# B-CAN-giraffe_v1.net
KiCad netlist of a schematic drawn in EAGLE
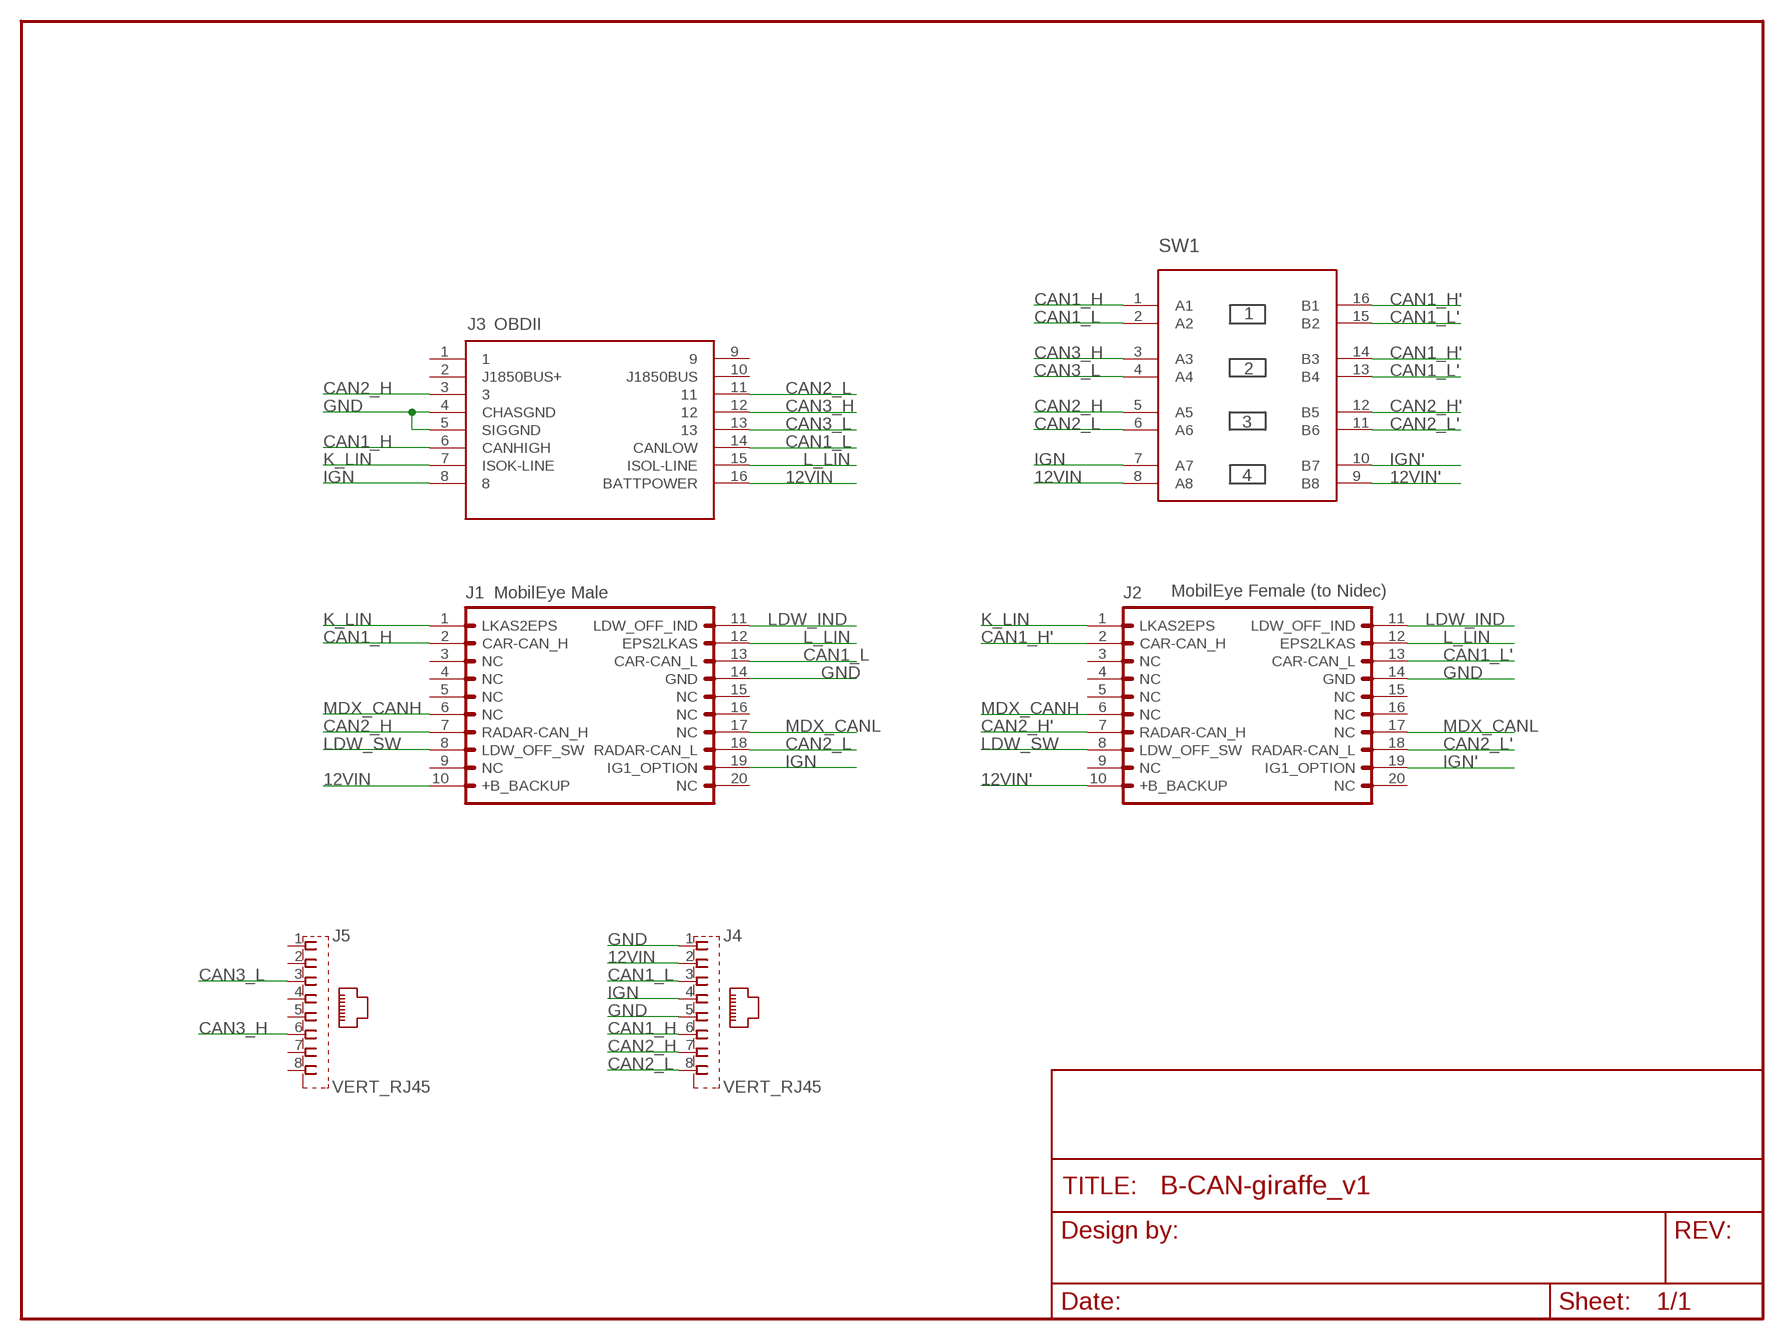
[diagram p0: schematic, sheet 1]

(export (version "E")
  (design (tool "Eeschema 10.0.6"))
  (components
    (comp (ref "FRAME1")
      (value "FRAME-LETTERNO_PACKAGE")
      (footprint "eagle-import:DUMMY")
      (fields (field (name "DESIGNER") "Nobody"))
      (libsource (lib "eagle-import") (part "FRAME-LETTERNO_PACKAGE"))
    )
    (comp (ref "J1")
      (value "MOBILEYERAMALE")
      (footprint "eagle-import:2X10(RA)")
      (libsource (lib "eagle-import") (part "MOBILEYERAMALE"))
    )
    (comp (ref "J2")
      (value "MOBILEYEFEMALE")
      (footprint "eagle-import:2X10(JAE_FEMALE)")
      (libsource (lib "eagle-import") (part "MOBILEYEFEMALE"))
    )
    (comp (ref "J3")
      (value "OBDII-FEMALE-CUT")
      (footprint "eagle-import:OBDII-FEMALE-MIDCUT")
      (libsource (lib "eagle-import") (part "OBDII-FEMALE-CUT"))
    )
    (comp (ref "J4")
      (value "VERT_RJ45")
      (footprint "eagle-import:GLX-S-88M")
      (libsource (lib "eagle-import") (part "VERT_RJ45"))
    )
    (comp (ref "J5")
      (value "VERT_RJ45")
      (footprint "eagle-import:GLX-S-88M")
      (libsource (lib "eagle-import") (part "comma.ai_2652900_VERT_RJ45"))
    )
    (comp (ref "SW1")
      (value "4XDPSTSMT")
      (footprint "eagle-import:4-DPST")
      (libsource (lib "eagle-import") (part "4XDPSTSMT"))
    )
  )
  (nets
    (net (code "1") (name "/12VIN") (class "Default")
      (node (ref "J1") (pin "10") (pinfunction "+B_BACKUP_10") (pintype "bidirectional"))
      (node (ref "J3") (pin "16") (pinfunction "BATTPOWER_16") (pintype "bidirectional"))
      (node (ref "J4") (pin "2") (pinfunction "2_2") (pintype "passive"))
      (node (ref "SW1") (pin "8") (pinfunction "A8_8") (pintype "bidirectional"))
    )
    (net (code "2") (name "/12VIN'") (class "Default")
      (node (ref "J2") (pin "10") (pinfunction "+B_BACKUP_10") (pintype "bidirectional"))
      (node (ref "SW1") (pin "9") (pinfunction "B8_9") (pintype "bidirectional"))
    )
    (net (code "3") (name "/CAN1_H") (class "Default")
      (node (ref "J1") (pin "2") (pinfunction "CAR-CAN_H_2") (pintype "bidirectional"))
      (node (ref "J3") (pin "6") (pinfunction "CANHIGH_6") (pintype "bidirectional"))
      (node (ref "J4") (pin "6") (pinfunction "6_6") (pintype "passive"))
      (node (ref "SW1") (pin "1") (pinfunction "A1_1") (pintype "bidirectional"))
    )
    (net (code "4") (name "/CAN1_H'") (class "Default")
      (node (ref "J2") (pin "2") (pinfunction "CAR-CAN_H_2") (pintype "bidirectional"))
      (node (ref "SW1") (pin "14") (pinfunction "B3_14") (pintype "bidirectional"))
      (node (ref "SW1") (pin "16") (pinfunction "B1_16") (pintype "bidirectional"))
    )
    (net (code "5") (name "/CAN1_L") (class "Default")
      (node (ref "J1") (pin "13") (pinfunction "CAR-CAN_L_13") (pintype "bidirectional"))
      (node (ref "J3") (pin "14") (pinfunction "CANLOW_14") (pintype "bidirectional"))
      (node (ref "J4") (pin "3") (pinfunction "3_3") (pintype "passive"))
      (node (ref "SW1") (pin "2") (pinfunction "A2_2") (pintype "bidirectional"))
    )
    (net (code "6") (name "/CAN1_L'") (class "Default")
      (node (ref "J2") (pin "13") (pinfunction "CAR-CAN_L_13") (pintype "bidirectional"))
      (node (ref "SW1") (pin "13") (pinfunction "B4_13") (pintype "bidirectional"))
      (node (ref "SW1") (pin "15") (pinfunction "B2_15") (pintype "bidirectional"))
    )
    (net (code "7") (name "/CAN2_H") (class "Default")
      (node (ref "J1") (pin "7") (pinfunction "RADAR-CAN_H_7") (pintype "bidirectional"))
      (node (ref "J3") (pin "3") (pinfunction "3_3") (pintype "bidirectional"))
      (node (ref "J4") (pin "7") (pinfunction "7_7") (pintype "passive"))
      (node (ref "SW1") (pin "5") (pinfunction "A5_5") (pintype "bidirectional"))
    )
    (net (code "8") (name "/CAN2_H'") (class "Default")
      (node (ref "J2") (pin "7") (pinfunction "RADAR-CAN_H_7") (pintype "bidirectional"))
      (node (ref "SW1") (pin "12") (pinfunction "B5_12") (pintype "bidirectional"))
    )
    (net (code "9") (name "/CAN2_L") (class "Default")
      (node (ref "J1") (pin "18") (pinfunction "RADAR-CAN_L_18") (pintype "bidirectional"))
      (node (ref "J3") (pin "11") (pinfunction "11_11") (pintype "bidirectional"))
      (node (ref "J4") (pin "8") (pinfunction "8_8") (pintype "passive"))
      (node (ref "SW1") (pin "6") (pinfunction "A6_6") (pintype "bidirectional"))
    )
    (net (code "10") (name "/CAN2_L'") (class "Default")
      (node (ref "J2") (pin "18") (pinfunction "RADAR-CAN_L_18") (pintype "bidirectional"))
      (node (ref "SW1") (pin "11") (pinfunction "B6_11") (pintype "bidirectional"))
    )
    (net (code "11") (name "/CAN3_H") (class "Default")
      (node (ref "J3") (pin "12") (pinfunction "12_12") (pintype "bidirectional"))
      (node (ref "J5") (pin "6") (pinfunction "6_6") (pintype "passive"))
      (node (ref "SW1") (pin "3") (pinfunction "A3_3") (pintype "bidirectional"))
    )
    (net (code "12") (name "/CAN3_L") (class "Default")
      (node (ref "J3") (pin "13") (pinfunction "13_13") (pintype "bidirectional"))
      (node (ref "J5") (pin "3") (pinfunction "3_3") (pintype "passive"))
      (node (ref "SW1") (pin "4") (pinfunction "A4_4") (pintype "bidirectional"))
    )
    (net (code "13") (name "/GND") (class "Default")
      (node (ref "J1") (pin "14") (pinfunction "GND_14") (pintype "bidirectional"))
      (node (ref "J2") (pin "14") (pinfunction "GND_14") (pintype "bidirectional"))
      (node (ref "J3") (pin "4") (pinfunction "CHASGND_4") (pintype "bidirectional"))
      (node (ref "J3") (pin "5") (pinfunction "SIGGND_5") (pintype "bidirectional"))
      (node (ref "J4") (pin "1") (pinfunction "1_1") (pintype "passive"))
      (node (ref "J4") (pin "5") (pinfunction "5_5") (pintype "passive"))
    )
    (net (code "14") (name "/IGN") (class "Default")
      (node (ref "J1") (pin "19") (pinfunction "IG1_OPTION_19") (pintype "bidirectional"))
      (node (ref "J3") (pin "8") (pinfunction "8_8") (pintype "bidirectional"))
      (node (ref "J4") (pin "4") (pinfunction "4_4") (pintype "passive"))
      (node (ref "SW1") (pin "7") (pinfunction "A7_7") (pintype "bidirectional"))
    )
    (net (code "15") (name "/IGN'") (class "Default")
      (node (ref "J2") (pin "19") (pinfunction "IG1_OPTION_19") (pintype "bidirectional"))
      (node (ref "SW1") (pin "10") (pinfunction "B7_10") (pintype "bidirectional"))
    )
    (net (code "16") (name "/K_LIN") (class "Default")
      (node (ref "J1") (pin "1") (pinfunction "LKAS2EPS_1") (pintype "bidirectional"))
      (node (ref "J2") (pin "1") (pinfunction "LKAS2EPS_1") (pintype "bidirectional"))
      (node (ref "J3") (pin "7") (pinfunction "ISOK-LINE_7") (pintype "bidirectional"))
    )
    (net (code "17") (name "/LDW_IND") (class "Default")
      (node (ref "J1") (pin "11") (pinfunction "LDW_OFF_IND_11") (pintype "bidirectional"))
      (node (ref "J2") (pin "11") (pinfunction "LDW_OFF_IND_11") (pintype "bidirectional"))
    )
    (net (code "18") (name "/LDW_SW") (class "Default")
      (node (ref "J1") (pin "8") (pinfunction "LDW_OFF_SW_8") (pintype "bidirectional"))
      (node (ref "J2") (pin "8") (pinfunction "LDW_OFF_SW_8") (pintype "bidirectional"))
    )
    (net (code "19") (name "/L_LIN") (class "Default")
      (node (ref "J1") (pin "12") (pinfunction "EPS2LKAS_12") (pintype "bidirectional"))
      (node (ref "J2") (pin "12") (pinfunction "EPS2LKAS_12") (pintype "bidirectional"))
      (node (ref "J3") (pin "15") (pinfunction "ISOL-LINE_15") (pintype "bidirectional"))
    )
    (net (code "20") (name "/MDX_CANH") (class "Default")
      (node (ref "J1") (pin "6") (pinfunction "NC_6") (pintype "bidirectional"))
      (node (ref "J2") (pin "6") (pinfunction "NC_6") (pintype "bidirectional"))
    )
    (net (code "21") (name "/MDX_CANL") (class "Default")
      (node (ref "J1") (pin "17") (pinfunction "NC_17") (pintype "bidirectional"))
      (node (ref "J2") (pin "17") (pinfunction "NC_17") (pintype "bidirectional"))
    )
    (net (code "22") (name "unconnected-(J1-NC-Pad3)") (class "Default")
      (node (ref "J1") (pin "3") (pinfunction "NC_3") (pintype "bidirectional"))
    )
    (net (code "23") (name "unconnected-(J1-NC-Pad4)") (class "Default")
      (node (ref "J1") (pin "4") (pinfunction "NC_4") (pintype "bidirectional"))
    )
    (net (code "24") (name "unconnected-(J1-NC-Pad5)") (class "Default")
      (node (ref "J1") (pin "5") (pinfunction "NC_5") (pintype "bidirectional"))
    )
    (net (code "25") (name "unconnected-(J1-NC-Pad9)") (class "Default")
      (node (ref "J1") (pin "9") (pinfunction "NC_9") (pintype "bidirectional"))
    )
    (net (code "26") (name "unconnected-(J1-NC-Pad15)") (class "Default")
      (node (ref "J1") (pin "15") (pinfunction "NC_15") (pintype "bidirectional"))
    )
    (net (code "27") (name "unconnected-(J1-NC-Pad16)") (class "Default")
      (node (ref "J1") (pin "16") (pinfunction "NC_16") (pintype "bidirectional"))
    )
    (net (code "28") (name "unconnected-(J1-NC-Pad20)") (class "Default")
      (node (ref "J1") (pin "20") (pinfunction "NC_20") (pintype "bidirectional"))
    )
    (net (code "29") (name "unconnected-(J2-NC-Pad3)") (class "Default")
      (node (ref "J2") (pin "3") (pinfunction "NC_3") (pintype "bidirectional"))
    )
    (net (code "30") (name "unconnected-(J2-NC-Pad4)") (class "Default")
      (node (ref "J2") (pin "4") (pinfunction "NC_4") (pintype "bidirectional"))
    )
    (net (code "31") (name "unconnected-(J2-NC-Pad5)") (class "Default")
      (node (ref "J2") (pin "5") (pinfunction "NC_5") (pintype "bidirectional"))
    )
    (net (code "32") (name "unconnected-(J2-NC-Pad9)") (class "Default")
      (node (ref "J2") (pin "9") (pinfunction "NC_9") (pintype "bidirectional"))
    )
    (net (code "33") (name "unconnected-(J2-NC-Pad15)") (class "Default")
      (node (ref "J2") (pin "15") (pinfunction "NC_15") (pintype "bidirectional"))
    )
    (net (code "34") (name "unconnected-(J2-NC-Pad16)") (class "Default")
      (node (ref "J2") (pin "16") (pinfunction "NC_16") (pintype "bidirectional"))
    )
    (net (code "35") (name "unconnected-(J2-NC-Pad20)") (class "Default")
      (node (ref "J2") (pin "20") (pinfunction "NC_20") (pintype "bidirectional"))
    )
    (net (code "36") (name "unconnected-(J3-J1850BUS+-Pad2)") (class "Default")
      (node (ref "J3") (pin "2") (pinfunction "J1850BUS+_2") (pintype "bidirectional"))
    )
    (net (code "37") (name "unconnected-(J3-J1850BUS-Pad10)") (class "Default")
      (node (ref "J3") (pin "10") (pinfunction "J1850BUS_10") (pintype "bidirectional"))
    )
    (net (code "38") (name "unconnected-(J3-Pad1)") (class "Default")
      (node (ref "J3") (pin "1") (pinfunction "1_1") (pintype "bidirectional"))
    )
    (net (code "39") (name "unconnected-(J3-Pad9)") (class "Default")
      (node (ref "J3") (pin "9") (pinfunction "9_9") (pintype "bidirectional"))
    )
    (net (code "40") (name "unconnected-(J5-Pad1)") (class "Default")
      (node (ref "J5") (pin "1") (pinfunction "1_1") (pintype "passive"))
    )
    (net (code "41") (name "unconnected-(J5-Pad2)") (class "Default")
      (node (ref "J5") (pin "2") (pinfunction "2_2") (pintype "passive"))
    )
    (net (code "42") (name "unconnected-(J5-Pad4)") (class "Default")
      (node (ref "J5") (pin "4") (pinfunction "4_4") (pintype "passive"))
    )
    (net (code "43") (name "unconnected-(J5-Pad5)") (class "Default")
      (node (ref "J5") (pin "5") (pinfunction "5_5") (pintype "passive"))
    )
    (net (code "44") (name "unconnected-(J5-Pad7)") (class "Default")
      (node (ref "J5") (pin "7") (pinfunction "7_7") (pintype "passive"))
    )
    (net (code "45") (name "unconnected-(J5-Pad8)") (class "Default")
      (node (ref "J5") (pin "8") (pinfunction "8_8") (pintype "passive"))
    )
  )
)
